# FEU-102-1_part4.net
KiCad netlist of a schematic drawn in Altium Designer
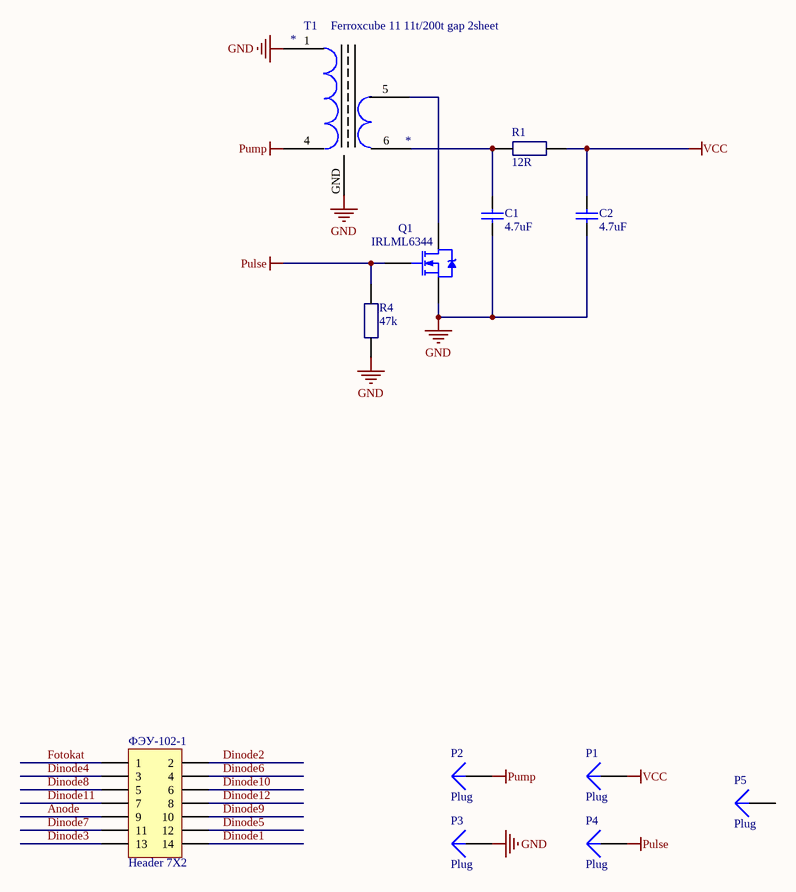
[diagram p0: FEU-102-1_part4.SchDoc]

(export (version "E")
  (design (tool "Eeschema 10.0.6"))
  (components
    (comp (ref "C1")
      (value "4.7uF")
      (footprint "Miscellaneous Devices:C1206")
      (description "Capacitor (Semiconductor SIM Model)")
      (fields (field (name "PUBLISHER") "Altium Limited"))
      (libsource (lib "Miscellaneous Devices") (part "Cap Semi"))
    )
    (comp (ref "C2")
      (value "4.7uF")
      (footprint "Miscellaneous Devices:C1206")
      (description "Capacitor (Semiconductor SIM Model)")
      (fields (field (name "PUBLISHER") "Altium Limited"))
      (libsource (lib "Miscellaneous Devices") (part "Cap Semi"))
    )
    (comp (ref "P1")
      (value "Plug")
      (footprint "PIN1")
      (fields (field (name "PUBLISHER") "Altium Limited"))
      (libsource (lib "Miscellaneous Connectors") (part "Plug"))
    )
    (comp (ref "P2")
      (value "Plug")
      (footprint "PIN1")
      (fields (field (name "PUBLISHER") "Altium Limited"))
      (libsource (lib "Miscellaneous Connectors") (part "Plug"))
    )
    (comp (ref "P3")
      (value "Plug")
      (footprint "PIN1")
      (fields (field (name "PUBLISHER") "Altium Limited"))
      (libsource (lib "Miscellaneous Connectors") (part "Plug"))
    )
    (comp (ref "P4")
      (value "Plug")
      (footprint "PIN1")
      (fields (field (name "PUBLISHER") "Altium Limited"))
      (libsource (lib "Miscellaneous Connectors") (part "Plug"))
    )
    (comp (ref "P5")
      (value "Plug")
      (footprint "PIN1")
      (fields (field (name "PUBLISHER") "Altium Limited"))
      (libsource (lib "Miscellaneous Connectors") (part "Plug"))
    )
    (comp (ref "Q1")
      (value "IRLML6344")
      (footprint "SOT-23_N")
      (description "HEXFET Power MOSFET")
      (fields (field (name "PUBLISHER") "Altium Limited"))
      (libsource (lib "IR Discrete MOSFET - Power") (part "IRLML2402"))
    )
    (comp (ref "R1")
      (value "12R")
      (footprint "1608[0603]_RES")
      (libsource (lib "Микрон-3") (part "Resistor 0805"))
    )
    (comp (ref "R4")
      (value "47k")
      (footprint "1608[0603]_RES")
      (libsource (lib "Микрон-3") (part "Resistor 0805"))
    )
    (comp (ref "T1")
      (value "Ferroxcube 11 11t/200t gap 2sheet")
      (footprint "Epcos ER9.5/5")
      (libsource (lib "My SCH library") (part "Epcos ER9.5/5"))
    )
    (comp (ref "ФЭУ-102-1")
      (value "Header 7X2")
      (footprint "ФЭУ-102")
      (description "Header, 7-Pin, Dual row")
      (fields (field (name "PUBLISHER") "Altium Limited"))
      (libsource (lib "Miscellaneous Connectors") (part "Header 7X2"))
    )
  )
  (nets
    (net (code "1") (name "/Anode") (class "Default")
      (node (ref "ФЭУ-102-1") (pin "9") (pinfunction "9_9") (pintype "passive"))
    )
    (net (code "2") (name "/Dinode1") (class "Default")
      (node (ref "ФЭУ-102-1") (pin "14") (pinfunction "14_14") (pintype "passive"))
    )
    (net (code "3") (name "/Dinode2") (class "Default")
      (node (ref "ФЭУ-102-1") (pin "2") (pinfunction "2_2") (pintype "passive"))
    )
    (net (code "4") (name "/Dinode3") (class "Default")
      (node (ref "ФЭУ-102-1") (pin "13") (pinfunction "13_13") (pintype "passive"))
    )
    (net (code "5") (name "/Dinode4") (class "Default")
      (node (ref "ФЭУ-102-1") (pin "3") (pinfunction "3_3") (pintype "passive"))
    )
    (net (code "6") (name "/Dinode5") (class "Default")
      (node (ref "ФЭУ-102-1") (pin "12") (pinfunction "12_12") (pintype "passive"))
    )
    (net (code "7") (name "/Dinode6") (class "Default")
      (node (ref "ФЭУ-102-1") (pin "4") (pinfunction "4_4") (pintype "passive"))
    )
    (net (code "8") (name "/Dinode7") (class "Default")
      (node (ref "ФЭУ-102-1") (pin "11") (pinfunction "11_11") (pintype "passive"))
    )
    (net (code "9") (name "/Dinode8") (class "Default")
      (node (ref "ФЭУ-102-1") (pin "5") (pinfunction "5_5") (pintype "passive"))
    )
    (net (code "10") (name "/Dinode9") (class "Default")
      (node (ref "ФЭУ-102-1") (pin "10") (pinfunction "10_10") (pintype "passive"))
    )
    (net (code "11") (name "/Dinode10") (class "Default")
      (node (ref "ФЭУ-102-1") (pin "6") (pinfunction "6_6") (pintype "passive"))
    )
    (net (code "12") (name "/Dinode11") (class "Default")
      (node (ref "ФЭУ-102-1") (pin "7") (pinfunction "7_7") (pintype "passive"))
    )
    (net (code "13") (name "/Dinode12") (class "Default")
      (node (ref "ФЭУ-102-1") (pin "8") (pinfunction "8_8") (pintype "passive"))
    )
    (net (code "14") (name "/Fotokat") (class "Default")
      (node (ref "ФЭУ-102-1") (pin "1") (pinfunction "1_1") (pintype "passive"))
    )
    (net (code "15") (name "GND") (class "Default")
      (node (ref "C1") (pin "2") (pinfunction "2_2") (pintype "passive"))
      (node (ref "C2") (pin "2") (pinfunction "2_2") (pintype "passive"))
      (node (ref "P3") (pin "1") (pinfunction "1_1") (pintype "passive"))
      (node (ref "Q1") (pin "2") (pinfunction "S_2") (pintype "passive"))
      (node (ref "R4") (pin "1") (pinfunction "A_1") (pintype "passive"))
      (node (ref "T1") (pin "1") (pinfunction "1_1") (pintype "passive"))
      (node (ref "T1") (pin "GND") (pinfunction "GND_GND") (pintype "passive"))
    )
    (net (code "16") (name "Net-(Q1-D)") (class "Default")
      (node (ref "Q1") (pin "3") (pinfunction "D_3") (pintype "passive"))
      (node (ref "T1") (pin "5") (pinfunction "5_5") (pintype "passive"))
    )
    (net (code "17") (name "Net-(R1-A)") (class "Default")
      (node (ref "C1") (pin "1") (pinfunction "1_1") (pintype "passive"))
      (node (ref "R1") (pin "1") (pinfunction "A_1") (pintype "passive"))
      (node (ref "T1") (pin "6") (pintype "passive"))
    )
    (net (code "18") (name "Pulse") (class "Default")
      (node (ref "P4") (pin "1") (pinfunction "1_1") (pintype "passive"))
      (node (ref "Q1") (pin "1") (pinfunction "G_1") (pintype "passive"))
      (node (ref "R4") (pin "2") (pinfunction "2_2") (pintype "passive"))
    )
    (net (code "19") (name "Pump") (class "Default")
      (node (ref "P2") (pin "1") (pinfunction "1_1") (pintype "passive"))
      (node (ref "T1") (pin "4") (pinfunction "4_4") (pintype "passive"))
    )
    (net (code "20") (name "VCC") (class "Default")
      (node (ref "C2") (pin "1") (pinfunction "1_1") (pintype "passive"))
      (node (ref "P1") (pin "1") (pinfunction "1_1") (pintype "passive"))
      (node (ref "R1") (pin "2") (pinfunction "2_2") (pintype "passive"))
    )
    (net (code "21") (name "unconnected-(P5-Pad1)") (class "Default")
      (node (ref "P5") (pin "1") (pinfunction "1_1") (pintype "passive"))
    )
  )
)
